# Control_Board.net
KiCad netlist of a schematic drawn in EAGLE
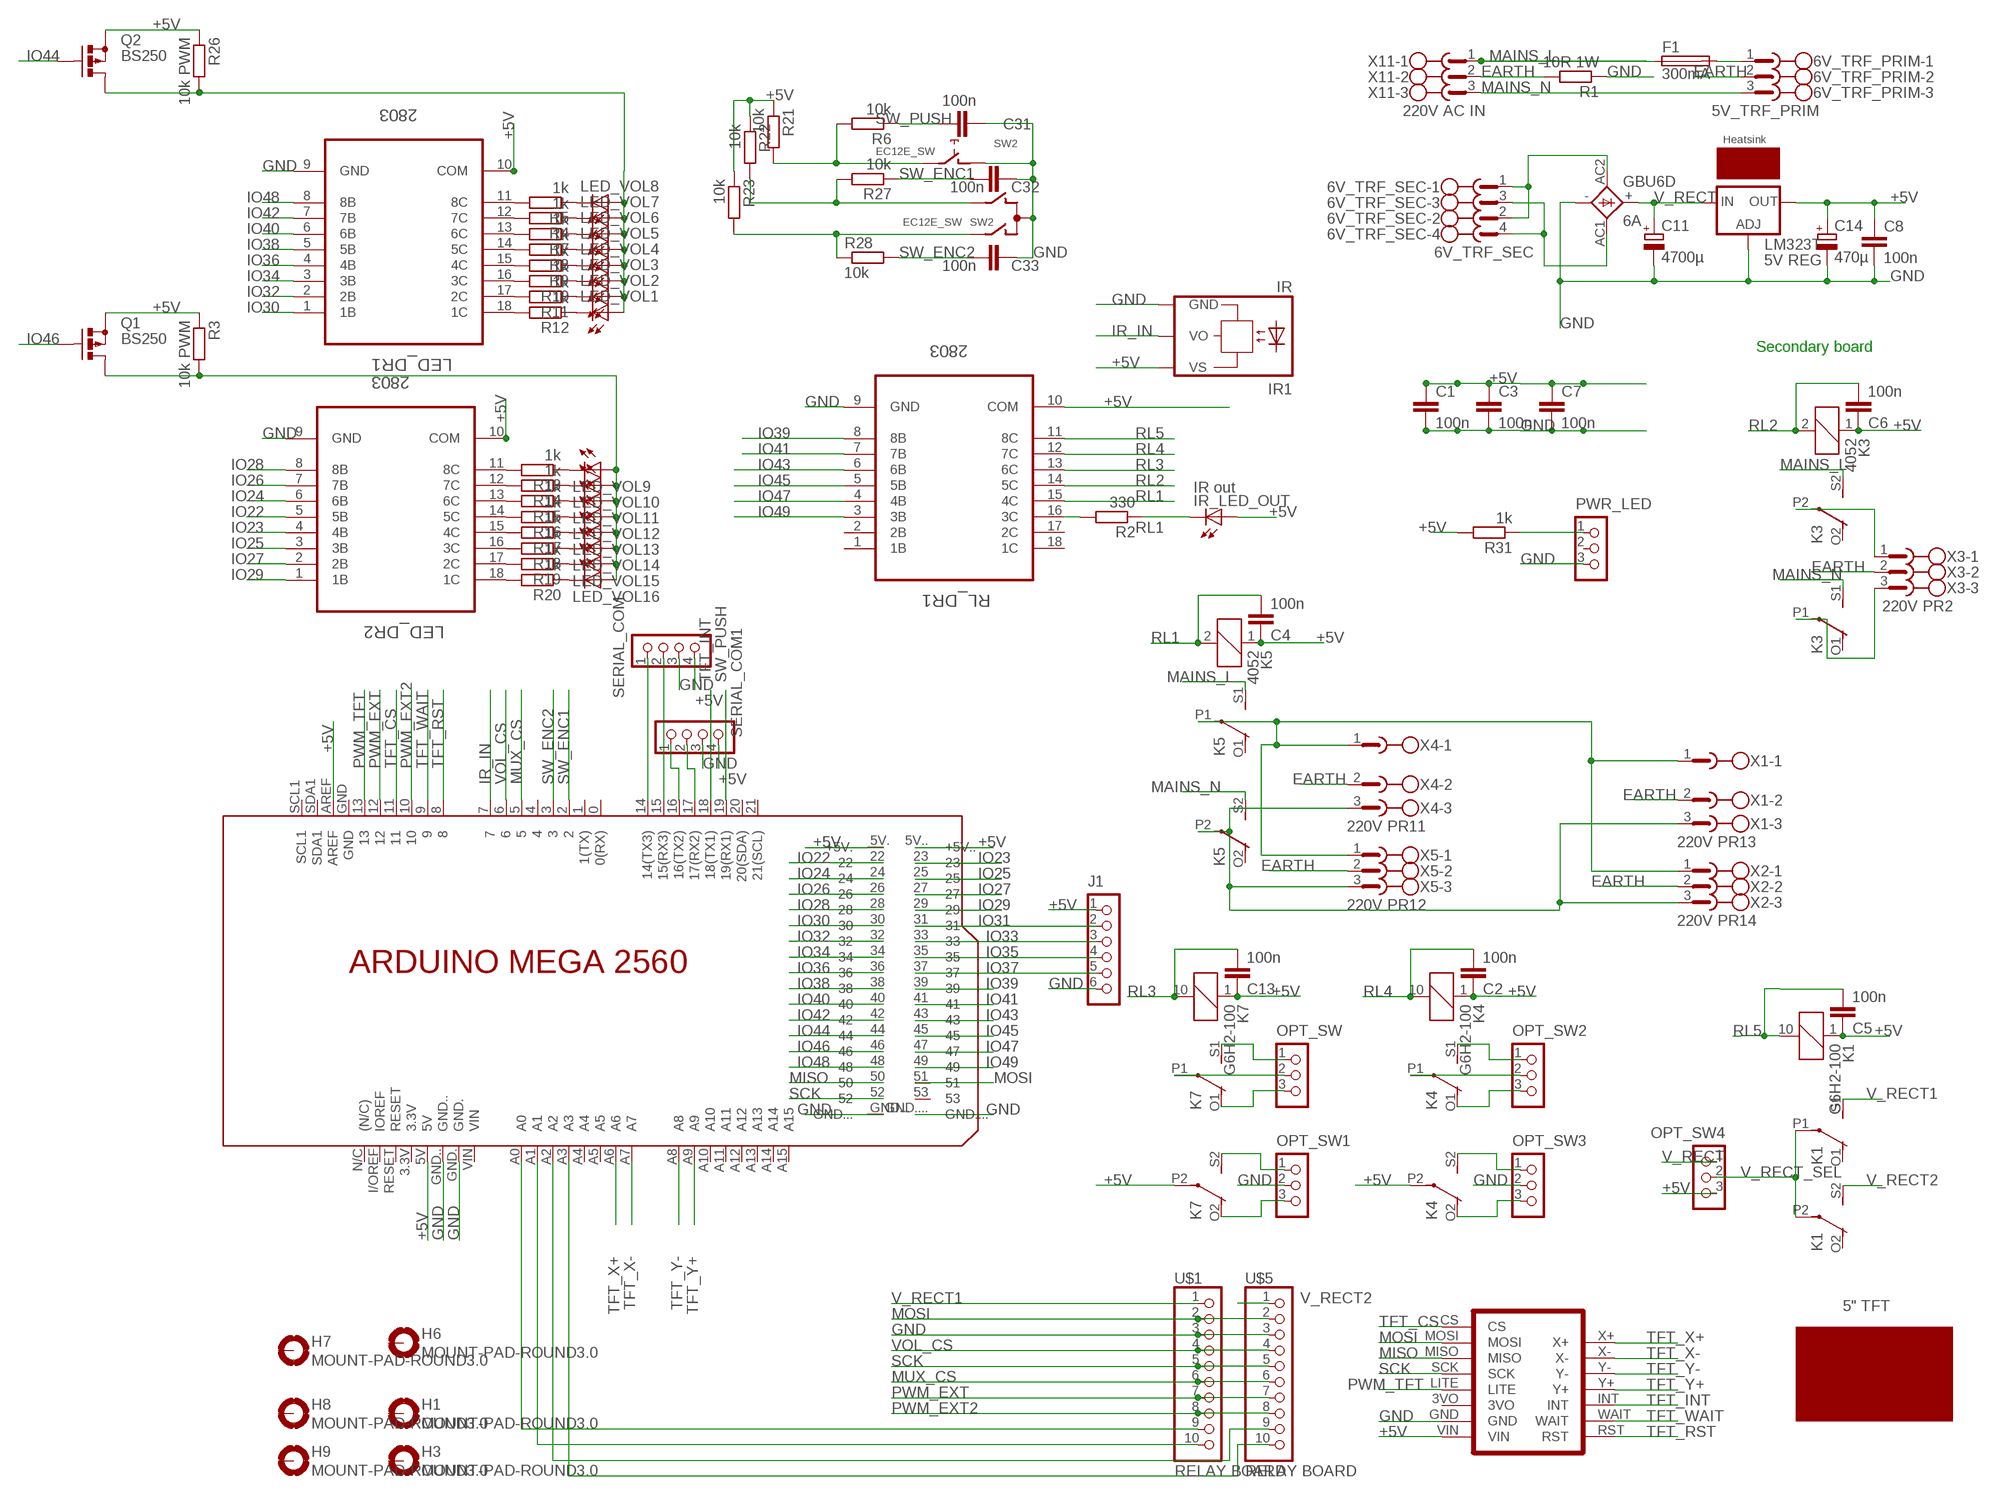
[diagram p0: schematic, sheet 1]

(export (version "E")
  (design (tool "Eeschema 10.0.6"))
  (components
    (comp (ref "6V_TRF_PRIM")
      (value "5V_TRF_PRIM")
      (footprint "eagle-import:MSTBV3")
      (fields
        (field (name "MPN") "MSTBV 2,5/3-GF-5.08")
        (field (name "MPN_1") "MSTBV 2,5/3-GF-5.08")
        (field (name "OC_FARNELL") "1792793")
        (field (name "OC_NEWARK") "69R9846")
      )
      (libsource (lib "eagle-import") (part "MSTBV3"))
    )
    (comp (ref "6V_TRF_SEC")
      (value "6V_TRF_SEC")
      (footprint "eagle-import:MSTBV4")
      (fields (field (name "MPN") "MSTBV 2,5/4-GF-5.08"))
      (libsource (lib "eagle-import") (part "MSTBV4"))
    )
    (comp (ref "C1")
      (value "100n")
      (footprint "eagle-import:C050-025X075")
      (libsource (lib "eagle-import") (part "C-EU050-025X075"))
    )
    (comp (ref "C2")
      (value "100n")
      (footprint "eagle-import:C050-025X075")
      (libsource (lib "eagle-import") (part "C-EU050-025X075"))
    )
    (comp (ref "C3")
      (value "100n")
      (footprint "eagle-import:C050-025X075")
      (libsource (lib "eagle-import") (part "C-EU050-025X075"))
    )
    (comp (ref "C4")
      (value "100n")
      (footprint "eagle-import:C050-025X075")
      (libsource (lib "eagle-import") (part "C-EU050-025X075"))
    )
    (comp (ref "C5")
      (value "100n")
      (footprint "eagle-import:C050-025X075")
      (libsource (lib "eagle-import") (part "C-EU050-025X075"))
    )
    (comp (ref "C6")
      (value "100n")
      (footprint "eagle-import:C050-025X075")
      (libsource (lib "eagle-import") (part "C-EU050-025X075"))
    )
    (comp (ref "C7")
      (value "100n")
      (footprint "eagle-import:C050-025X075")
      (libsource (lib "eagle-import") (part "C-EU050-025X075"))
    )
    (comp (ref "C8")
      (value "100n")
      (footprint "eagle-import:C050-025X075")
      (libsource (lib "eagle-import") (part "C-EU050-025X075"))
    )
    (comp (ref "C11")
      (value "4700µ")
      (footprint "eagle-import:E7,5-16")
      (libsource (lib "eagle-import") (part "CPOL-EUE7.5-16"))
    )
    (comp (ref "C13")
      (value "100n")
      (footprint "eagle-import:C050-025X075")
      (libsource (lib "eagle-import") (part "C-EU050-025X075"))
    )
    (comp (ref "C14")
      (value "470µ")
      (footprint "eagle-import:E2,5-6")
      (libsource (lib "eagle-import") (part "CPOL-EUE2.5-6"))
    )
    (comp (ref "C31")
      (value "100n")
      (footprint "eagle-import:C050-025X075")
      (libsource (lib "eagle-import") (part "C-EU050-025X075"))
    )
    (comp (ref "C32")
      (value "100n")
      (footprint "eagle-import:C050-025X075")
      (libsource (lib "eagle-import") (part "C-EU050-025X075"))
    )
    (comp (ref "C33")
      (value "100n")
      (footprint "eagle-import:C050-025X075")
      (libsource (lib "eagle-import") (part "C-EU050-025X075"))
    )
    (comp (ref "F1")
      (value "300mA")
      (footprint "eagle-import:GSH15")
      (fields (field (name "MPN") "64900001039"))
      (libsource (lib "eagle-import") (part "GSH15"))
    )
    (comp (ref "GBU6D")
      (value "6A")
      (footprint "eagle-import:GBU4S")
      (libsource (lib "eagle-import") (part "GBU4"))
    )
    (comp (ref "H1")
      (value "MOUNT-PAD-ROUND3.0")
      (footprint "eagle-import:3,0-PAD")
      (libsource (lib "eagle-import") (part "MOUNT-PAD-ROUND3.0"))
    )
    (comp (ref "H3")
      (value "MOUNT-PAD-ROUND3.0")
      (footprint "eagle-import:3,0-PAD")
      (libsource (lib "eagle-import") (part "MOUNT-PAD-ROUND3.0"))
    )
    (comp (ref "H6")
      (value "MOUNT-PAD-ROUND3.0")
      (footprint "eagle-import:3,0-PAD")
      (libsource (lib "eagle-import") (part "MOUNT-PAD-ROUND3.0"))
    )
    (comp (ref "H7")
      (value "MOUNT-PAD-ROUND3.0")
      (footprint "eagle-import:3,0-PAD")
      (libsource (lib "eagle-import") (part "MOUNT-PAD-ROUND3.0"))
    )
    (comp (ref "H8")
      (value "MOUNT-PAD-ROUND3.0")
      (footprint "eagle-import:3,0-PAD")
      (libsource (lib "eagle-import") (part "MOUNT-PAD-ROUND3.0"))
    )
    (comp (ref "H9")
      (value "MOUNT-PAD-ROUND3.0")
      (footprint "eagle-import:3,0-PAD")
      (libsource (lib "eagle-import") (part "MOUNT-PAD-ROUND3.0"))
    )
    (comp (ref "IR1")
      (value "IR")
      (footprint "eagle-import:TSOP17_TB1")
      (libsource (lib "eagle-import") (part "TSOP17TB138"))
    )
    (comp (ref "IR_LED_OUT")
      (value "IR out")
      (footprint "eagle-import:LED3MM")
      (fields
        (field (name "MF") "VISHAY SEMICONDUCTOR")
        (field (name "MF_1") "VISHAY SEMICONDUCTOR")
        (field (name "OC_FARNELL") "1612435")
      )
      (libsource (lib "eagle-import") (part "TLLG4400"))
    )
    (comp (ref "J1")
      (value "CON_HEADER_1X06-PTH")
      (footprint "eagle-import:M1X6")
      (libsource (lib "eagle-import") (part "CON_HEADER_1X06-PTH"))
    )
    (comp (ref "K1")
      (value "G6H2-100")
      (footprint "eagle-import:G6H2-100")
      (fields (field (name "OC_FARNELL") "unknown") (field (name "OC_NEWARK") "unknown"))
      (libsource (lib "eagle-import") (part "G6H2-100"))
    )
    (comp (ref "K3")
      (value "4052")
      (footprint "eagle-import:F4052")
      (libsource (lib "eagle-import") (part "4052"))
    )
    (comp (ref "K4")
      (value "G6H2-100")
      (footprint "eagle-import:G6H2-100")
      (libsource (lib "eagle-import") (part "G6H2-100"))
    )
    (comp (ref "K5")
      (value "4052")
      (footprint "eagle-import:F4052")
      (libsource (lib "eagle-import") (part "4052"))
    )
    (comp (ref "K7")
      (value "G6H2-100")
      (footprint "eagle-import:G6H2-100")
      (libsource (lib "eagle-import") (part "G6H2-100"))
    )
    (comp (ref "LED_DR1")
      (value "2803")
      (footprint "eagle-import:SOIC127P1030X265-18N")
      (fields
        (field (name "MPN") "ULN2803ADWR")
        (field (name "MPN_1") "ULN2803ADWR")
        (field (name "OC_FARNELL") "1652420")
        (field (name "OC_NEWARK") "87H4769")
        (field (name "PACKAGE") "SOIC-18")
        (field (name "SUPPLIER") "TEXAS INSTRUMENTS")
      )
      (libsource (lib "eagle-import") (part "ULN2803ADWR"))
    )
    (comp (ref "LED_DR2")
      (value "2803")
      (footprint "eagle-import:SOIC127P1030X265-18N")
      (fields
        (field (name "MPN") "ULN2803ADWR")
        (field (name "MPN_1") "ULN2803ADWR")
        (field (name "OC_FARNELL") "1652420")
        (field (name "OC_NEWARK") "87H4769")
        (field (name "PACKAGE") "SOIC-18")
        (field (name "SUPPLIER") "TEXAS INSTRUMENTS")
      )
      (libsource (lib "eagle-import") (part "ULN2803ADWR"))
    )
    (comp (ref "LED_VOL1")
      (value "TLLG4400")
      (footprint "eagle-import:LED3MM")
      (fields
        (field (name "MF") "VISHAY SEMICONDUCTOR")
        (field (name "MF_1") "VISHAY SEMICONDUCTOR")
        (field (name "OC_FARNELL") "1612435")
      )
      (libsource (lib "eagle-import") (part "TLLG4400"))
    )
    (comp (ref "LED_VOL2")
      (value "TLLG4400")
      (footprint "eagle-import:LED3MM")
      (fields
        (field (name "MF") "VISHAY SEMICONDUCTOR")
        (field (name "MF_1") "VISHAY SEMICONDUCTOR")
        (field (name "OC_FARNELL") "1612435")
      )
      (libsource (lib "eagle-import") (part "TLLG4400"))
    )
    (comp (ref "LED_VOL3")
      (value "TLLG4400")
      (footprint "eagle-import:LED3MM")
      (fields
        (field (name "MF") "VISHAY SEMICONDUCTOR")
        (field (name "MF_1") "VISHAY SEMICONDUCTOR")
        (field (name "OC_FARNELL") "1612435")
      )
      (libsource (lib "eagle-import") (part "TLLG4400"))
    )
    (comp (ref "LED_VOL4")
      (value "TLLG4400")
      (footprint "eagle-import:LED3MM")
      (fields
        (field (name "MF") "VISHAY SEMICONDUCTOR")
        (field (name "MF_1") "VISHAY SEMICONDUCTOR")
        (field (name "OC_FARNELL") "1612435")
      )
      (libsource (lib "eagle-import") (part "TLLG4400"))
    )
    (comp (ref "LED_VOL5")
      (value "TLLG4400")
      (footprint "eagle-import:LED3MM")
      (fields
        (field (name "MF") "VISHAY SEMICONDUCTOR")
        (field (name "MF_1") "VISHAY SEMICONDUCTOR")
        (field (name "OC_FARNELL") "1612435")
      )
      (libsource (lib "eagle-import") (part "TLLG4400"))
    )
    (comp (ref "LED_VOL6")
      (value "TLLG4400")
      (footprint "eagle-import:LED3MM")
      (fields
        (field (name "MF") "VISHAY SEMICONDUCTOR")
        (field (name "MF_1") "VISHAY SEMICONDUCTOR")
        (field (name "OC_FARNELL") "1612435")
      )
      (libsource (lib "eagle-import") (part "TLLG4400"))
    )
    (comp (ref "LED_VOL7")
      (value "TLLG4400")
      (footprint "eagle-import:LED3MM")
      (fields
        (field (name "MF") "VISHAY SEMICONDUCTOR")
        (field (name "MF_1") "VISHAY SEMICONDUCTOR")
        (field (name "OC_FARNELL") "1612435")
      )
      (libsource (lib "eagle-import") (part "TLLG4400"))
    )
    (comp (ref "LED_VOL8")
      (value "TLLG4400")
      (footprint "eagle-import:LED3MM")
      (fields
        (field (name "MF") "VISHAY SEMICONDUCTOR")
        (field (name "MF_1") "VISHAY SEMICONDUCTOR")
        (field (name "OC_FARNELL") "1612435")
      )
      (libsource (lib "eagle-import") (part "TLLG4400"))
    )
    (comp (ref "LED_VOL9")
      (value "TLLG4400")
      (footprint "eagle-import:LED3MM")
      (fields
        (field (name "MF") "VISHAY SEMICONDUCTOR")
        (field (name "MF_1") "VISHAY SEMICONDUCTOR")
        (field (name "OC_FARNELL") "1612435")
      )
      (libsource (lib "eagle-import") (part "TLLG4400"))
    )
    (comp (ref "LED_VOL10")
      (value "TLLG4400")
      (footprint "eagle-import:LED3MM")
      (fields
        (field (name "MF") "VISHAY SEMICONDUCTOR")
        (field (name "MF_1") "VISHAY SEMICONDUCTOR")
        (field (name "OC_FARNELL") "1612435")
      )
      (libsource (lib "eagle-import") (part "TLLG4400"))
    )
    (comp (ref "LED_VOL11")
      (value "TLLG4400")
      (footprint "eagle-import:LED3MM")
      (fields
        (field (name "MF") "VISHAY SEMICONDUCTOR")
        (field (name "MF_1") "VISHAY SEMICONDUCTOR")
        (field (name "OC_FARNELL") "1612435")
      )
      (libsource (lib "eagle-import") (part "TLLG4400"))
    )
    (comp (ref "LED_VOL12")
      (value "TLLG4400")
      (footprint "eagle-import:LED3MM")
      (fields
        (field (name "MF") "VISHAY SEMICONDUCTOR")
        (field (name "MF_1") "VISHAY SEMICONDUCTOR")
        (field (name "OC_FARNELL") "1612435")
      )
      (libsource (lib "eagle-import") (part "TLLG4400"))
    )
    (comp (ref "LED_VOL13")
      (value "TLLG4400")
      (footprint "eagle-import:LED3MM")
      (fields
        (field (name "MF") "VISHAY SEMICONDUCTOR")
        (field (name "MF_1") "VISHAY SEMICONDUCTOR")
        (field (name "OC_FARNELL") "1612435")
      )
      (libsource (lib "eagle-import") (part "TLLG4400"))
    )
    (comp (ref "LED_VOL14")
      (value "TLLG4400")
      (footprint "eagle-import:LED3MM")
      (fields
        (field (name "MF") "VISHAY SEMICONDUCTOR")
        (field (name "MF_1") "VISHAY SEMICONDUCTOR")
        (field (name "OC_FARNELL") "1612435")
      )
      (libsource (lib "eagle-import") (part "TLLG4400"))
    )
    (comp (ref "LED_VOL15")
      (value "TLLG4400")
      (footprint "eagle-import:LED3MM")
      (fields
        (field (name "MF") "VISHAY SEMICONDUCTOR")
        (field (name "MF_1") "VISHAY SEMICONDUCTOR")
        (field (name "OC_FARNELL") "1612435")
      )
      (libsource (lib "eagle-import") (part "TLLG4400"))
    )
    (comp (ref "LED_VOL16")
      (value "TLLG4400")
      (footprint "eagle-import:LED3MM")
      (fields
        (field (name "MF") "VISHAY SEMICONDUCTOR")
        (field (name "MF_1") "VISHAY SEMICONDUCTOR")
        (field (name "OC_FARNELL") "1612435")
      )
      (libsource (lib "eagle-import") (part "TLLG4400"))
    )
    (comp (ref "LM323T")
      (value "5V REG")
      (footprint "eagle-import:TO220S")
      (libsource (lib "eagle-import") (part "LM138-TSTO220S_IAO"))
    )
    (comp (ref "OPT_SW")
      (value "CON_HEADER_1X03-PTH")
      (footprint "eagle-import:M1X3")
      (libsource (lib "eagle-import") (part "CON_HEADER_1X03-PTH"))
    )
    (comp (ref "OPT_SW1")
      (value "CON_HEADER_1X03-PTH")
      (footprint "eagle-import:M1X3")
      (libsource (lib "eagle-import") (part "CON_HEADER_1X03-PTH"))
    )
    (comp (ref "OPT_SW2")
      (value "CON_HEADER_1X03-PTH")
      (footprint "eagle-import:M1X3")
      (libsource (lib "eagle-import") (part "CON_HEADER_1X03-PTH"))
    )
    (comp (ref "OPT_SW3")
      (value "CON_HEADER_1X03-PTH")
      (footprint "eagle-import:M1X3")
      (libsource (lib "eagle-import") (part "CON_HEADER_1X03-PTH"))
    )
    (comp (ref "OPT_SW4")
      (value "V_RECT_-_5V_OUT")
      (footprint "eagle-import:M1X3")
      (libsource (lib "eagle-import") (part "CON_HEADER_1X03-PTH"))
    )
    (comp (ref "PCB2")
      (value "ARDUINO_MEGA2560_INV")
      (footprint "eagle-import:ARDUINO_MEGA2560_INV")
      (libsource (lib "eagle-import") (part "ARDUINO_MEGA2560_INV"))
    )
    (comp (ref "PWR_LED")
      (value "CON_HEADER_1X03-PTH")
      (footprint "eagle-import:M1X3")
      (libsource (lib "eagle-import") (part "CON_HEADER_1X03-PTH"))
    )
    (comp (ref "Q1")
      (value "BS250")
      (footprint "eagle-import:SOT54E")
      (libsource (lib "eagle-import") (part "BS250"))
    )
    (comp (ref "Q2")
      (value "BS250")
      (footprint "eagle-import:SOT54E")
      (libsource (lib "eagle-import") (part "BS250"))
    )
    (comp (ref "R1")
      (value "10R 1W")
      (footprint "eagle-import:0411_15")
      (libsource (lib "eagle-import") (part "R-EU_0411/15"))
    )
    (comp (ref "R2")
      (value "330")
      (footprint "eagle-import:0207_10")
      (libsource (lib "eagle-import") (part "R-EU_0207/10"))
    )
    (comp (ref "R3")
      (value "10k PWM")
      (footprint "eagle-import:0207_10")
      (libsource (lib "eagle-import") (part "R-EU_0207/10"))
    )
    (comp (ref "R4")
      (value "1k")
      (footprint "eagle-import:0207_10")
      (libsource (lib "eagle-import") (part "R-EU_0207/10"))
    )
    (comp (ref "R5")
      (value "1k")
      (footprint "eagle-import:0207_10")
      (libsource (lib "eagle-import") (part "R-EU_0207/10"))
    )
    (comp (ref "R6")
      (value "10k")
      (footprint "eagle-import:0207_10")
      (libsource (lib "eagle-import") (part "R-EU_0207/10"))
    )
    (comp (ref "R7")
      (value "1k")
      (footprint "eagle-import:0207_10")
      (libsource (lib "eagle-import") (part "R-EU_0207/10"))
    )
    (comp (ref "R8")
      (value "1k")
      (footprint "eagle-import:0207_10")
      (libsource (lib "eagle-import") (part "R-EU_0207/10"))
    )
    (comp (ref "R9")
      (value "1k")
      (footprint "eagle-import:0207_10")
      (libsource (lib "eagle-import") (part "R-EU_0207/10"))
    )
    (comp (ref "R10")
      (value "1k")
      (footprint "eagle-import:0207_10")
      (libsource (lib "eagle-import") (part "R-EU_0207/10"))
    )
    (comp (ref "R11")
      (value "1k")
      (footprint "eagle-import:0207_10")
      (libsource (lib "eagle-import") (part "R-EU_0207/10"))
    )
    (comp (ref "R12")
      (value "1k")
      (footprint "eagle-import:0207_10")
      (libsource (lib "eagle-import") (part "R-EU_0207/10"))
    )
    (comp (ref "R13")
      (value "1k")
      (footprint "eagle-import:0207_10")
      (libsource (lib "eagle-import") (part "R-EU_0207/10"))
    )
    (comp (ref "R14")
      (value "1k")
      (footprint "eagle-import:0207_10")
      (libsource (lib "eagle-import") (part "R-EU_0207/10"))
    )
    (comp (ref "R15")
      (value "1k")
      (footprint "eagle-import:0207_10")
      (libsource (lib "eagle-import") (part "R-EU_0207/10"))
    )
    (comp (ref "R16")
      (value "1k")
      (footprint "eagle-import:0207_10")
      (libsource (lib "eagle-import") (part "R-EU_0207/10"))
    )
    (comp (ref "R17")
      (value "1k")
      (footprint "eagle-import:0207_10")
      (libsource (lib "eagle-import") (part "R-EU_0207/10"))
    )
    (comp (ref "R18")
      (value "1k")
      (footprint "eagle-import:0207_10")
      (libsource (lib "eagle-import") (part "R-EU_0207/10"))
    )
    (comp (ref "R19")
      (value "1k")
      (footprint "eagle-import:0207_10")
      (libsource (lib "eagle-import") (part "R-EU_0207/10"))
    )
    (comp (ref "R20")
      (value "1k")
      (footprint "eagle-import:0207_10")
      (libsource (lib "eagle-import") (part "R-EU_0207/10"))
    )
    (comp (ref "R21")
      (value "10k")
      (footprint "eagle-import:0207_10")
      (libsource (lib "eagle-import") (part "R-EU_0207/10"))
    )
    (comp (ref "R22")
      (value "10k")
      (footprint "eagle-import:0207_10")
      (libsource (lib "eagle-import") (part "R-EU_0207/10"))
    )
    (comp (ref "R23")
      (value "10k")
      (footprint "eagle-import:0207_10")
      (libsource (lib "eagle-import") (part "R-EU_0207/10"))
    )
    (comp (ref "R26")
      (value "10k PWM")
      (footprint "eagle-import:0207_10")
      (libsource (lib "eagle-import") (part "R-EU_0207/10"))
    )
    (comp (ref "R27")
      (value "10k")
      (footprint "eagle-import:0207_10")
      (libsource (lib "eagle-import") (part "R-EU_0207/10"))
    )
    (comp (ref "R28")
      (value "10k")
      (footprint "eagle-import:0207_10")
      (libsource (lib "eagle-import") (part "R-EU_0207/10"))
    )
    (comp (ref "R31")
      (value "1k")
      (footprint "eagle-import:0207_10")
      (libsource (lib "eagle-import") (part "R-EU_0207/10"))
    )
    (comp (ref "RL_DR1")
      (value "2803")
      (footprint "eagle-import:SOIC127P1030X265-18N")
      (fields
        (field (name "MPN") "ULN2803ADWR")
        (field (name "MPN_1") "ULN2803ADWR")
        (field (name "OC_FARNELL") "1652420")
        (field (name "OC_NEWARK") "87H4769")
        (field (name "PACKAGE") "SOIC-18")
        (field (name "SUPPLIER") "TEXAS INSTRUMENTS")
      )
      (libsource (lib "eagle-import") (part "ULN2803ADWR"))
    )
    (comp (ref "SERIAL_COM")
      (value "CON_HEADER_1X04")
      (footprint "eagle-import:M1X4")
      (libsource (lib "eagle-import") (part "CON_HEADER_1X04"))
    )
    (comp (ref "SERIAL_COM1")
      (value "CON_HEADER_1X04")
      (footprint "eagle-import:M1X4")
      (libsource (lib "eagle-import") (part "CON_HEADER_1X04"))
    )
    (comp (ref "SW2")
      (value "EC12E_SW")
      (footprint "eagle-import:ALPS_EC12E_SW")
      (fields (field (name "MPN") "EC12E2424407"))
      (libsource (lib "eagle-import") (part "EC12E_SW"))
    )
    (comp (ref "U$1")
      (value "RELAY BOARD")
      (footprint "eagle-import:1X10-BIG")
      (libsource (lib "eagle-import") (part "PINHD-1X10"))
    )
    (comp (ref "U$2")
      (value "HEATSINK")
      (footprint "eagle-import:HEATSINK")
      (libsource (lib "eagle-import") (part "HEATSINK"))
    )
    (comp (ref "U$3")
      (value "RA8875")
      (footprint "eagle-import:RA8875")
      (libsource (lib "eagle-import") (part "RA8875"))
    )
    (comp (ref "U$4")
      (value "5\"TFT")
      (footprint "eagle-import:5_TFT")
      (libsource (lib "eagle-import") (part "5{dblquote}TFT"))
    )
    (comp (ref "U$5")
      (value "RELAY BOARD")
      (footprint "eagle-import:1X10-BIG")
      (libsource (lib "eagle-import") (part "PINHD-1X10"))
    )
    (comp (ref "X1")
      (value "220V PR13")
      (footprint "eagle-import:MSTBV3")
      (fields (field (name "MPN") "MSTBV 2,5/3-GF-5.08"))
      (libsource (lib "eagle-import") (part "MSTBV3"))
    )
    (comp (ref "X2")
      (value "220V PR14")
      (footprint "eagle-import:MSTBV3")
      (fields
        (field (name "MPN") "MSTBV 2,5/3-GF-5.08")
        (field (name "MPN_1") "MSTBV 2,5/3-GF-5.08")
        (field (name "OC_FARNELL") "1792793")
        (field (name "OC_NEWARK") "69R9846")
      )
      (libsource (lib "eagle-import") (part "MSTBV3"))
    )
    (comp (ref "X3")
      (value "220V PR2")
      (footprint "eagle-import:MSTBV3")
      (fields (field (name "MPN") "MSTBV 2,5/3-GF-5.08"))
      (libsource (lib "eagle-import") (part "MSTBV3"))
    )
    (comp (ref "X4")
      (value "220V PR11")
      (footprint "eagle-import:MSTBV3")
      (fields
        (field (name "MPN") "MSTBV 2,5/3-GF-5.08")
        (field (name "MPN_1") "MSTBV 2,5/3-GF-5.08")
        (field (name "OC_FARNELL") "1792793")
        (field (name "OC_NEWARK") "69R9846")
      )
      (libsource (lib "eagle-import") (part "MSTBV3"))
    )
    (comp (ref "X5")
      (value "220V PR12")
      (footprint "eagle-import:MSTBV3")
      (fields
        (field (name "MPN") "MSTBV 2,5/3-GF-5.08")
        (field (name "MPN_1") "MSTBV 2,5/3-GF-5.08")
        (field (name "OC_FARNELL") "1792793")
        (field (name "OC_NEWARK") "69R9846")
      )
      (libsource (lib "eagle-import") (part "MSTBV3"))
    )
    (comp (ref "X11")
      (value "220V AC IN")
      (footprint "eagle-import:MSTBV3")
      (fields (field (name "MPN") "MSTBV 2,5/3-GF-5.08"))
      (libsource (lib "eagle-import") (part "MSTBV3"))
    )
  )
  (nets
    (net (code "1") (name "/+5V") (class "Default")
      (node (ref "C1") (pin "1") (pinfunction "1_1") (pintype "passive"))
      (node (ref "C13") (pin "1") (pinfunction "1_1") (pintype "passive"))
      (node (ref "C14") (pin "+") (pinfunction "+_+") (pintype "passive"))
      (node (ref "C2") (pin "1") (pinfunction "1_1") (pintype "passive"))
      (node (ref "C3") (pin "1") (pinfunction "1_1") (pintype "passive"))
      (node (ref "C4") (pin "1") (pinfunction "1_1") (pintype "passive"))
      (node (ref "C5") (pin "1") (pinfunction "1_1") (pintype "passive"))
      (node (ref "C6") (pin "1") (pinfunction "1_1") (pintype "passive"))
      (node (ref "C7") (pin "1") (pinfunction "1_1") (pintype "passive"))
      (node (ref "C8") (pin "1") (pinfunction "1_1") (pintype "passive"))
      (node (ref "IR1") (pin "VS") (pinfunction "VS_VS") (pintype "power_in"))
      (node (ref "IR_LED_OUT") (pin "A") (pinfunction "A_A") (pintype "passive"))
      (node (ref "J1") (pin "1") (pinfunction "1_1") (pintype "bidirectional"))
      (node (ref "K1") (pin "1") (pinfunction "1_1") (pintype "passive"))
      (node (ref "K3") (pin "1") (pinfunction "1_1") (pintype "passive"))
      (node (ref "K4") (pin "1") (pinfunction "1_1") (pintype "passive"))
      (node (ref "K4") (pin "P2") (pinfunction "P_P2") (pintype "passive"))
      (node (ref "K5") (pin "1") (pinfunction "1_1") (pintype "passive"))
      (node (ref "K7") (pin "1") (pinfunction "1_1") (pintype "passive"))
      (node (ref "K7") (pin "P2") (pinfunction "P_P2") (pintype "passive"))
      (node (ref "LED_DR1") (pin "10") (pinfunction "COM_10") (pintype "output"))
      (node (ref "LED_DR2") (pin "10") (pinfunction "COM_10") (pintype "output"))
      (node (ref "LM323T") (pin "3") (pinfunction "OUT_3") (pintype "passive"))
      (node (ref "OPT_SW4") (pin "3") (pinfunction "3_3") (pintype "bidirectional"))
      (node (ref "PCB2") (pin "5V") (pinfunction "5V_5V") (pintype "bidirectional"))
      (node (ref "PCB2") (pin "5V.") (pinfunction "+5V._5V.") (pintype "bidirectional"))
      (node (ref "PCB2") (pin "5V..") (pinfunction "+5V.._5V..") (pintype "bidirectional"))
      (node (ref "PCB2") (pin "AREF") (pinfunction "AREF_AREF") (pintype "bidirectional"))
      (node (ref "Q1") (pin "S") (pinfunction "S_S") (pintype "passive"))
      (node (ref "Q2") (pin "S") (pinfunction "S_S") (pintype "passive"))
      (node (ref "R21") (pin "1") (pinfunction "1_1") (pintype "passive"))
      (node (ref "R22") (pin "1") (pinfunction "1_1") (pintype "passive"))
      (node (ref "R23") (pin "1") (pinfunction "1_1") (pintype "passive"))
      (node (ref "R26") (pin "1") (pinfunction "1_1") (pintype "passive"))
      (node (ref "R3") (pin "1") (pinfunction "1_1") (pintype "passive"))
      (node (ref "R31") (pin "2") (pinfunction "2_2") (pintype "passive"))
      (node (ref "RL_DR1") (pin "10") (pinfunction "COM_10") (pintype "output"))
      (node (ref "SERIAL_COM") (pin "4") (pinfunction "4_4") (pintype "bidirectional"))
      (node (ref "SERIAL_COM1") (pin "4") (pinfunction "4_4") (pintype "bidirectional"))
      (node (ref "U$3") (pin "VIN") (pinfunction "VIN_VIN") (pintype "bidirectional"))
    )
    (net (code "2") (name "/EARTH") (class "Default")
      (node (ref "6V_TRF_PRIM") (pin "2") (pinfunction "1_2") (pintype "passive"))
      (node (ref "R1") (pin "2") (pinfunction "2_2") (pintype "passive"))
      (node (ref "X1") (pin "2") (pinfunction "1_2") (pintype "passive"))
      (node (ref "X11") (pin "2") (pinfunction "1_2") (pintype "passive"))
      (node (ref "X2") (pin "2") (pinfunction "1_2") (pintype "passive"))
      (node (ref "X3") (pin "2") (pinfunction "1_2") (pintype "passive"))
      (node (ref "X4") (pin "2") (pinfunction "1_2") (pintype "passive"))
      (node (ref "X5") (pin "2") (pinfunction "1_2") (pintype "passive"))
    )
    (net (code "3") (name "/GND") (class "Default")
      (node (ref "C1") (pin "2") (pinfunction "2_2") (pintype "passive"))
      (node (ref "C11") (pin "-") (pinfunction "-_-") (pintype "passive"))
      (node (ref "C14") (pin "-") (pinfunction "-_-") (pintype "passive"))
      (node (ref "C3") (pin "2") (pinfunction "2_2") (pintype "passive"))
      (node (ref "C31") (pin "1") (pinfunction "1_1") (pintype "passive"))
      (node (ref "C32") (pin "1") (pinfunction "1_1") (pintype "passive"))
      (node (ref "C33") (pin "1") (pinfunction "1_1") (pintype "passive"))
      (node (ref "C7") (pin "2") (pinfunction "2_2") (pintype "passive"))
      (node (ref "C8") (pin "2") (pinfunction "2_2") (pintype "passive"))
      (node (ref "GBU6D") (pin "-") (pinfunction "-_-") (pintype "passive"))
      (node (ref "IR1") (pin "GND") (pinfunction "GND_GND") (pintype "power_in"))
      (node (ref "J1") (pin "6") (pinfunction "6_6") (pintype "passive"))
      (node (ref "LED_DR1") (pin "9") (pinfunction "GND_9") (pintype "passive"))
      (node (ref "LED_DR2") (pin "9") (pinfunction "GND_9") (pintype "passive"))
      (node (ref "LM323T") (pin "2") (pinfunction "ADJ_2") (pintype "input"))
      (node (ref "OPT_SW1") (pin "2") (pinfunction "2_2") (pintype "bidirectional"))
      (node (ref "OPT_SW3") (pin "2") (pinfunction "2_2") (pintype "bidirectional"))
      (node (ref "PCB2") (pin "GND.") (pinfunction "GND._GND.") (pintype "bidirectional"))
      (node (ref "PCB2") (pin "GND..") (pinfunction "GND.._GND..") (pintype "bidirectional"))
      (node (ref "PCB2") (pin "GND...") (pinfunction "GND..._GND...") (pintype "bidirectional"))
      (node (ref "PCB2") (pin "GND....") (pinfunction "GND...._GND....") (pintype "bidirectional"))
      (node (ref "PWR_LED") (pin "3") (pinfunction "3_3") (pintype "bidirectional"))
      (node (ref "R1") (pin "1") (pinfunction "1_1") (pintype "passive"))
      (node (ref "RL_DR1") (pin "9") (pinfunction "GND_9") (pintype "passive"))
      (node (ref "SERIAL_COM") (pin "3") (pinfunction "3_3") (pintype "bidirectional"))
      (node (ref "SERIAL_COM1") (pin "3") (pinfunction "3_3") (pintype "bidirectional"))
      (node (ref "SW2") (pin "C") (pinfunction "C_C") (pintype "passive"))
      (node (ref "SW2") (pin "D") (pinfunction "1_D") (pintype "passive"))
      (node (ref "U$1") (pin "3") (pinfunction "3_3") (pintype "passive"))
      (node (ref "U$3") (pin "GND") (pinfunction "GND_GND") (pintype "bidirectional"))
      (node (ref "U$5") (pin "3") (pinfunction "3_3") (pintype "passive"))
    )
    (net (code "4") (name "/IO22") (class "Default")
      (node (ref "LED_DR2") (pin "5") (pinfunction "5B_5") (pintype "input"))
      (node (ref "PCB2") (pin "22") (pinfunction "22_22") (pintype "bidirectional"))
    )
    (net (code "5") (name "/IO23") (class "Default")
      (node (ref "LED_DR2") (pin "4") (pinfunction "4B_4") (pintype "input"))
      (node (ref "PCB2") (pin "23") (pinfunction "23_23") (pintype "bidirectional"))
    )
    (net (code "6") (name "/IO24") (class "Default")
      (node (ref "LED_DR2") (pin "6") (pinfunction "6B_6") (pintype "input"))
      (node (ref "PCB2") (pin "24") (pinfunction "24_24") (pintype "bidirectional"))
    )
    (net (code "7") (name "/IO25") (class "Default")
      (node (ref "LED_DR2") (pin "3") (pinfunction "3B_3") (pintype "input"))
      (node (ref "PCB2") (pin "25") (pinfunction "25_25") (pintype "bidirectional"))
    )
    (net (code "8") (name "/IO26") (class "Default")
      (node (ref "LED_DR2") (pin "7") (pinfunction "7B_7") (pintype "input"))
      (node (ref "PCB2") (pin "26") (pinfunction "26_26") (pintype "bidirectional"))
    )
    (net (code "9") (name "/IO27") (class "Default")
      (node (ref "LED_DR2") (pin "2") (pinfunction "2B_2") (pintype "input"))
      (node (ref "PCB2") (pin "27") (pinfunction "27_27") (pintype "bidirectional"))
    )
    (net (code "10") (name "/IO28") (class "Default")
      (node (ref "LED_DR2") (pin "8") (pinfunction "8B_8") (pintype "input"))
      (node (ref "PCB2") (pin "28") (pinfunction "28_28") (pintype "bidirectional"))
    )
    (net (code "11") (name "/IO29") (class "Default")
      (node (ref "LED_DR2") (pin "1") (pinfunction "1B_1") (pintype "input"))
      (node (ref "PCB2") (pin "29") (pinfunction "29_29") (pintype "bidirectional"))
    )
    (net (code "12") (name "/IO30") (class "Default")
      (node (ref "LED_DR1") (pin "1") (pinfunction "1B_1") (pintype "input"))
      (node (ref "PCB2") (pin "30") (pinfunction "30_30") (pintype "bidirectional"))
    )
    (net (code "13") (name "/IO31") (class "Default")
      (node (ref "J1") (pin "2") (pinfunction "2_2") (pintype "bidirectional"))
      (node (ref "PCB2") (pin "31") (pinfunction "31_31") (pintype "bidirectional"))
    )
    (net (code "14") (name "/IO32") (class "Default")
      (node (ref "LED_DR1") (pin "2") (pinfunction "2B_2") (pintype "input"))
      (node (ref "PCB2") (pin "32") (pinfunction "32_32") (pintype "bidirectional"))
    )
    (net (code "15") (name "/IO33") (class "Default")
      (node (ref "J1") (pin "3") (pinfunction "3_3") (pintype "passive"))
      (node (ref "PCB2") (pin "33") (pinfunction "33_33") (pintype "bidirectional"))
    )
    (net (code "16") (name "/IO34") (class "Default")
      (node (ref "LED_DR1") (pin "3") (pinfunction "3B_3") (pintype "input"))
      (node (ref "PCB2") (pin "34") (pinfunction "34_34") (pintype "bidirectional"))
    )
    (net (code "17") (name "/IO35") (class "Default")
      (node (ref "J1") (pin "4") (pinfunction "4_4") (pintype "passive"))
      (node (ref "PCB2") (pin "35") (pinfunction "35_35") (pintype "bidirectional"))
    )
    (net (code "18") (name "/IO36") (class "Default")
      (node (ref "LED_DR1") (pin "4") (pinfunction "4B_4") (pintype "input"))
      (node (ref "PCB2") (pin "36") (pinfunction "36_36") (pintype "bidirectional"))
    )
    (net (code "19") (name "/IO37") (class "Default")
      (node (ref "J1") (pin "5") (pinfunction "5_5") (pintype "passive"))
      (node (ref "PCB2") (pin "37") (pinfunction "37_37") (pintype "bidirectional"))
    )
    (net (code "20") (name "/IO38") (class "Default")
      (node (ref "LED_DR1") (pin "5") (pinfunction "5B_5") (pintype "input"))
      (node (ref "PCB2") (pin "38") (pinfunction "38_38") (pintype "bidirectional"))
    )
    (net (code "21") (name "/IO39") (class "Default")
      (node (ref "PCB2") (pin "39") (pinfunction "39_39") (pintype "bidirectional"))
      (node (ref "RL_DR1") (pin "8") (pinfunction "8B_8") (pintype "input"))
    )
    (net (code "22") (name "/IO40") (class "Default")
      (node (ref "LED_DR1") (pin "6") (pinfunction "6B_6") (pintype "input"))
      (node (ref "PCB2") (pin "40") (pinfunction "40_40") (pintype "bidirectional"))
    )
    (net (code "23") (name "/IO41") (class "Default")
      (node (ref "PCB2") (pin "41") (pinfunction "41_41") (pintype "bidirectional"))
      (node (ref "RL_DR1") (pin "7") (pinfunction "7B_7") (pintype "input"))
    )
    (net (code "24") (name "/IO42") (class "Default")
      (node (ref "LED_DR1") (pin "7") (pinfunction "7B_7") (pintype "input"))
      (node (ref "PCB2") (pin "42") (pinfunction "42_42") (pintype "bidirectional"))
    )
    (net (code "25") (name "/IO43") (class "Default")
      (node (ref "PCB2") (pin "43") (pinfunction "43_43") (pintype "bidirectional"))
      (node (ref "RL_DR1") (pin "6") (pinfunction "6B_6") (pintype "input"))
    )
    (net (code "26") (name "/IO44") (class "Default")
      (node (ref "PCB2") (pin "44") (pinfunction "44_44") (pintype "bidirectional"))
      (node (ref "Q2") (pin "G") (pinfunction "G_G") (pintype "passive"))
    )
    (net (code "27") (name "/IO45") (class "Default")
      (node (ref "PCB2") (pin "45") (pinfunction "45_45") (pintype "bidirectional"))
      (node (ref "RL_DR1") (pin "5") (pinfunction "5B_5") (pintype "input"))
    )
    (net (code "28") (name "/IO46") (class "Default")
      (node (ref "PCB2") (pin "46") (pinfunction "46_46") (pintype "bidirectional"))
      (node (ref "Q1") (pin "G") (pinfunction "G_G") (pintype "passive"))
    )
    (net (code "29") (name "/IO47") (class "Default")
      (node (ref "PCB2") (pin "47") (pinfunction "47_47") (pintype "bidirectional"))
      (node (ref "RL_DR1") (pin "4") (pinfunction "4B_4") (pintype "input"))
    )
    (net (code "30") (name "/IO48") (class "Default")
      (node (ref "LED_DR1") (pin "8") (pinfunction "8B_8") (pintype "input"))
      (node (ref "PCB2") (pin "48") (pinfunction "48_48") (pintype "bidirectional"))
    )
    (net (code "31") (name "/IO49") (class "Default")
      (node (ref "PCB2") (pin "49") (pinfunction "49_49") (pintype "bidirectional"))
      (node (ref "RL_DR1") (pin "3") (pinfunction "3B_3") (pintype "input"))
    )
    (net (code "32") (name "/IR_IN") (class "Default")
      (node (ref "IR1") (pin "VO") (pinfunction "VO_VO") (pintype "open_collector"))
      (node (ref "PCB2") (pin "7") (pinfunction "7_7") (pintype "bidirectional"))
    )
    (net (code "33") (name "/MAINS_L") (class "Default")
      (node (ref "F1") (pin "1") (pinfunction "1_1") (pintype "passive"))
      (node (ref "K3") (pin "S2") (pinfunction "S_S2") (pintype "passive"))
      (node (ref "K5") (pin "S1") (pinfunction "S_S1") (pintype "passive"))
      (node (ref "X11") (pin "1") (pinfunction "1_1") (pintype "passive"))
    )
    (net (code "34") (name "/MAINS_N") (class "Default")
      (node (ref "6V_TRF_PRIM") (pin "3") (pinfunction "1_3") (pintype "passive"))
      (node (ref "K3") (pin "S1") (pinfunction "S_S1") (pintype "passive"))
      (node (ref "K5") (pin "S2") (pinfunction "S_S2") (pintype "passive"))
      (node (ref "X11") (pin "3") (pinfunction "1_3") (pintype "passive"))
    )
    (net (code "35") (name "/MISO") (class "Default")
      (node (ref "PCB2") (pin "50") (pinfunction "50_50") (pintype "bidirectional"))
      (node (ref "U$3") (pin "MISO") (pinfunction "MISO_MISO") (pintype "bidirectional"))
    )
    (net (code "36") (name "/MOSI") (class "Default")
      (node (ref "PCB2") (pin "51") (pinfunction "51_51") (pintype "bidirectional"))
      (node (ref "U$1") (pin "2") (pinfunction "2_2") (pintype "passive"))
      (node (ref "U$3") (pin "MOSI") (pinfunction "MOSI_MOSI") (pintype "bidirectional"))
      (node (ref "U$5") (pin "2") (pinfunction "2_2") (pintype "passive"))
    )
    (net (code "37") (name "/MUX_CS") (class "Default")
      (node (ref "PCB2") (pin "5") (pinfunction "5_5") (pintype "bidirectional"))
      (node (ref "U$1") (pin "6") (pinfunction "6_6") (pintype "passive"))
      (node (ref "U$5") (pin "6") (pinfunction "6_6") (pintype "passive"))
    )
    (net (code "38") (name "/PWM_EXT") (class "Default")
      (node (ref "PCB2") (pin "12") (pinfunction "12_12") (pintype "bidirectional"))
      (node (ref "U$1") (pin "7") (pinfunction "7_7") (pintype "passive"))
      (node (ref "U$5") (pin "7") (pinfunction "7_7") (pintype "passive"))
    )
    (net (code "39") (name "/PWM_EXT2") (class "Default")
      (node (ref "PCB2") (pin "10") (pinfunction "10_10") (pintype "bidirectional"))
      (node (ref "U$1") (pin "8") (pinfunction "8_8") (pintype "passive"))
      (node (ref "U$5") (pin "8") (pinfunction "8_8") (pintype "passive"))
    )
    (net (code "40") (name "/PWM_TFT") (class "Default")
      (node (ref "PCB2") (pin "13") (pinfunction "13_13") (pintype "bidirectional"))
      (node (ref "U$3") (pin "LITE") (pinfunction "LITE_LITE") (pintype "bidirectional"))
    )
    (net (code "41") (name "/RL1") (class "Default")
      (node (ref "C4") (pin "2") (pinfunction "2_2") (pintype "passive"))
      (node (ref "K5") (pin "2") (pinfunction "2_2") (pintype "passive"))
      (node (ref "RL_DR1") (pin "15") (pinfunction "4C_15") (pintype "output"))
    )
    (net (code "42") (name "/RL2") (class "Default")
      (node (ref "C6") (pin "2") (pinfunction "2_2") (pintype "passive"))
      (node (ref "K3") (pin "2") (pinfunction "2_2") (pintype "passive"))
      (node (ref "RL_DR1") (pin "14") (pinfunction "5C_14") (pintype "output"))
    )
    (net (code "43") (name "/RL3") (class "Default")
      (node (ref "C13") (pin "2") (pinfunction "2_2") (pintype "passive"))
      (node (ref "K7") (pin "10") (pinfunction "2_10") (pintype "passive"))
      (node (ref "RL_DR1") (pin "13") (pinfunction "6C_13") (pintype "output"))
    )
    (net (code "44") (name "/RL4") (class "Default")
      (node (ref "C2") (pin "2") (pinfunction "2_2") (pintype "passive"))
      (node (ref "K4") (pin "10") (pinfunction "2_10") (pintype "passive"))
      (node (ref "RL_DR1") (pin "12") (pinfunction "7C_12") (pintype "output"))
    )
    (net (code "45") (name "/RL5") (class "Default")
      (node (ref "C5") (pin "2") (pinfunction "2_2") (pintype "passive"))
      (node (ref "K1") (pin "10") (pinfunction "2_10") (pintype "passive"))
      (node (ref "RL_DR1") (pin "11") (pinfunction "8C_11") (pintype "output"))
    )
    (net (code "46") (name "/SCK") (class "Default")
      (node (ref "PCB2") (pin "52") (pinfunction "52_52") (pintype "bidirectional"))
      (node (ref "U$1") (pin "5") (pinfunction "5_5") (pintype "passive"))
      (node (ref "U$3") (pin "SCK") (pinfunction "SCK_SCK") (pintype "bidirectional"))
      (node (ref "U$5") (pin "5") (pinfunction "5_5") (pintype "passive"))
    )
    (net (code "47") (name "/SW_ENC1") (class "Default")
      (node (ref "C32") (pin "2") (pinfunction "2_2") (pintype "passive"))
      (node (ref "PCB2") (pin "2") (pinfunction "2_2") (pintype "bidirectional"))
      (node (ref "R27") (pin "1") (pinfunction "1_1") (pintype "passive"))
    )
    (net (code "48") (name "/SW_ENC2") (class "Default")
      (node (ref "C33") (pin "2") (pinfunction "2_2") (pintype "passive"))
      (node (ref "PCB2") (pin "3") (pinfunction "3_3") (pintype "bidirectional"))
      (node (ref "R28") (pin "2") (pinfunction "2_2") (pintype "passive"))
    )
    (net (code "49") (name "/SW_PUSH") (class "Default")
      (node (ref "C31") (pin "2") (pinfunction "2_2") (pintype "passive"))
      (node (ref "PCB2") (pin "19") (pinfunction "19(RX1)_19") (pintype "bidirectional"))
      (node (ref "R6") (pin "1") (pinfunction "1_1") (pintype "passive"))
    )
    (net (code "50") (name "/TFT_CS") (class "Default")
      (node (ref "PCB2") (pin "11") (pinfunction "11_11") (pintype "bidirectional"))
      (node (ref "U$3") (pin "CS") (pinfunction "CS_CS") (pintype "bidirectional"))
    )
    (net (code "51") (name "/TFT_INT") (class "Default")
      (node (ref "PCB2") (pin "18") (pinfunction "18(TX1)_18") (pintype "bidirectional"))
      (node (ref "U$3") (pin "INT") (pinfunction "INT_INT") (pintype "bidirectional"))
    )
    (net (code "52") (name "/TFT_RST") (class "Default")
      (node (ref "PCB2") (pin "8") (pinfunction "8_8") (pintype "bidirectional"))
      (node (ref "U$3") (pin "RST") (pinfunction "RST_RST") (pintype "bidirectional"))
    )
    (net (code "53") (name "/TFT_WAIT") (class "Default")
      (node (ref "PCB2") (pin "9") (pinfunction "9_9") (pintype "bidirectional"))
      (node (ref "U$3") (pin "WAIT") (pinfunction "WAIT_WAIT") (pintype "bidirectional"))
    )
    (net (code "54") (name "/TFT_X+") (class "Default")
      (node (ref "PCB2") (pin "A6") (pinfunction "A6_A6") (pintype "bidirectional"))
      (node (ref "U$3") (pin "X+") (pinfunction "X+_X+") (pintype "bidirectional"))
    )
    (net (code "55") (name "/TFT_X-") (class "Default")
      (node (ref "PCB2") (pin "A7") (pinfunction "A7_A7") (pintype "bidirectional"))
      (node (ref "U$3") (pin "X-") (pinfunction "X-_X-") (pintype "bidirectional"))
    )
    (net (code "56") (name "/TFT_Y+") (class "Default")
      (node (ref "PCB2") (pin "A9") (pinfunction "A9_A9") (pintype "bidirectional"))
      (node (ref "U$3") (pin "Y+") (pinfunction "Y+_Y+") (pintype "bidirectional"))
    )
    (net (code "57") (name "/TFT_Y-") (class "Default")
      (node (ref "PCB2") (pin "A8") (pinfunction "A8_A8") (pintype "bidirectional"))
      (node (ref "U$3") (pin "Y-") (pinfunction "Y-_Y-") (pintype "bidirectional"))
    )
    (net (code "58") (name "/VOL_CS") (class "Default")
      (node (ref "PCB2") (pin "6") (pinfunction "6_6") (pintype "bidirectional"))
      (node (ref "U$1") (pin "4") (pinfunction "4_4") (pintype "passive"))
      (node (ref "U$5") (pin "4") (pinfunction "4_4") (pintype "passive"))
    )
    (net (code "59") (name "/V_RECT") (class "Default")
      (node (ref "C11") (pin "+") (pinfunction "+_+") (pintype "passive"))
      (node (ref "GBU6D") (pin "+") (pinfunction "+_+") (pintype "passive"))
      (node (ref "LM323T") (pin "1") (pinfunction "IN_1") (pintype "input"))
      (node (ref "OPT_SW4") (pin "1") (pinfunction "1_1") (pintype "bidirectional"))
    )
    (net (code "60") (name "/V_RECT1") (class "Default")
      (node (ref "K1") (pin "S1") (pinfunction "S_S1") (pintype "passive"))
      (node (ref "U$1") (pin "1") (pinfunction "1_1") (pintype "passive"))
    )
    (net (code "61") (name "/V_RECT2") (class "Default")
      (node (ref "K1") (pin "S2") (pinfunction "S_S2") (pintype "passive"))
      (node (ref "U$5") (pin "1") (pinfunction "1_1") (pintype "passive"))
    )
    (net (code "62") (name "/V_RECT_SEL") (class "Default")
      (node (ref "K1") (pin "P1") (pinfunction "P_P1") (pintype "passive"))
      (node (ref "K1") (pin "P2") (pinfunction "P_P2") (pintype "passive"))
      (node (ref "OPT_SW4") (pin "2") (pinfunction "2_2") (pintype "bidirectional"))
    )
    (net (code "63") (name "Net-(6V_TRF_PRIM-Pad1)") (class "Default")
      (node (ref "6V_TRF_PRIM") (pin "1") (pinfunction "1_1") (pintype "passive"))
      (node (ref "F1") (pin "2") (pinfunction "2_2") (pintype "passive"))
    )
    (net (code "64") (name "Net-(6V_TRF_SECB-1)") (class "Default")
      (node (ref "6V_TRF_SEC") (pin "1") (pinfunction "1_1") (pintype "passive"))
      (node (ref "6V_TRF_SEC") (pin "2") (pinfunction "1_2") (pintype "passive"))
      (node (ref "GBU6D") (pin "AC2") (pinfunction "AC1_AC2") (pintype "passive"))
    )
    (net (code "65") (name "Net-(6V_TRF_SECC-1)") (class "Default")
      (node (ref "6V_TRF_SEC") (pin "3") (pinfunction "1_3") (pintype "passive"))
      (node (ref "6V_TRF_SEC") (pin "4") (pinfunction "1_4") (pintype "passive"))
      (node (ref "GBU6D") (pin "AC1") (pinfunction "AC2_AC1") (pintype "passive"))
    )
    (net (code "66") (name "Net-(IR_LED_OUT-C)") (class "Default")
      (node (ref "IR_LED_OUT") (pin "K") (pinfunction "C_K") (pintype "passive"))
      (node (ref "R2") (pin "1") (pinfunction "1_1") (pintype "passive"))
    )
    (net (code "67") (name "Net-(K3B-P)") (class "Default")
      (node (ref "K3") (pin "P1") (pinfunction "P_P1") (pintype "passive"))
      (node (ref "X3") (pin "3") (pinfunction "1_3") (pintype "passive"))
    )
    (net (code "68") (name "Net-(K3C-P)") (class "Default")
      (node (ref "K3") (pin "P2") (pinfunction "P_P2") (pintype "passive"))
      (node (ref "X3") (pin "1") (pinfunction "1_1") (pintype "passive"))
    )
    (net (code "69") (name "Net-(K4B-O)") (class "Default")
      (node (ref "K4") (pin "O1") (pinfunction "O_O1") (pintype "passive"))
      (node (ref "OPT_SW2") (pin "3") (pinfunction "3_3") (pintype "bidirectional"))
    )
    (net (code "70") (name "Net-(K4B-P)") (class "Default")
      (node (ref "K4") (pin "P1") (pinfunction "P_P1") (pintype "passive"))
      (node (ref "OPT_SW2") (pin "2") (pinfunction "2_2") (pintype "bidirectional"))
    )
    (net (code "71") (name "Net-(K4B-S)") (class "Default")
      (node (ref "K4") (pin "S1") (pinfunction "S_S1") (pintype "passive"))
      (node (ref "OPT_SW2") (pin "1") (pinfunction "1_1") (pintype "bidirectional"))
    )
    (net (code "72") (name "Net-(K4C-O)") (class "Default")
      (node (ref "K4") (pin "O2") (pinfunction "O_O2") (pintype "passive"))
      (node (ref "OPT_SW3") (pin "3") (pinfunction "3_3") (pintype "bidirectional"))
    )
    (net (code "73") (name "Net-(K4C-S)") (class "Default")
      (node (ref "K4") (pin "S2") (pinfunction "S_S2") (pintype "passive"))
      (node (ref "OPT_SW3") (pin "1") (pinfunction "1_1") (pintype "bidirectional"))
    )
    (net (code "74") (name "Net-(K5B-P)") (class "Default")
      (node (ref "K5") (pin "P1") (pinfunction "P_P1") (pintype "passive"))
      (node (ref "X1") (pin "1") (pinfunction "1_1") (pintype "passive"))
      (node (ref "X2") (pin "1") (pinfunction "1_1") (pintype "passive"))
      (node (ref "X4") (pin "1") (pinfunction "1_1") (pintype "passive"))
      (node (ref "X5") (pin "1") (pinfunction "1_1") (pintype "passive"))
    )
    (net (code "75") (name "Net-(K5C-P)") (class "Default")
      (node (ref "K5") (pin "P2") (pinfunction "P_P2") (pintype "passive"))
      (node (ref "X1") (pin "3") (pinfunction "1_3") (pintype "passive"))
      (node (ref "X2") (pin "3") (pinfunction "1_3") (pintype "passive"))
      (node (ref "X4") (pin "3") (pinfunction "1_3") (pintype "passive"))
      (node (ref "X5") (pin "3") (pinfunction "1_3") (pintype "passive"))
    )
    (net (code "76") (name "Net-(K7B-O)") (class "Default")
      (node (ref "K7") (pin "O1") (pinfunction "O_O1") (pintype "passive"))
      (node (ref "OPT_SW") (pin "3") (pinfunction "3_3") (pintype "bidirectional"))
    )
    (net (code "77") (name "Net-(K7B-P)") (class "Default")
      (node (ref "K7") (pin "P1") (pinfunction "P_P1") (pintype "passive"))
      (node (ref "OPT_SW") (pin "2") (pinfunction "2_2") (pintype "bidirectional"))
    )
    (net (code "78") (name "Net-(K7B-S)") (class "Default")
      (node (ref "K7") (pin "S1") (pinfunction "S_S1") (pintype "passive"))
      (node (ref "OPT_SW") (pin "1") (pinfunction "1_1") (pintype "bidirectional"))
    )
    (net (code "79") (name "Net-(K7C-O)") (class "Default")
      (node (ref "K7") (pin "O2") (pinfunction "O_O2") (pintype "passive"))
      (node (ref "OPT_SW1") (pin "3") (pinfunction "3_3") (pintype "bidirectional"))
    )
    (net (code "80") (name "Net-(K7C-S)") (class "Default")
      (node (ref "K7") (pin "S2") (pinfunction "S_S2") (pintype "passive"))
      (node (ref "OPT_SW1") (pin "1") (pinfunction "1_1") (pintype "bidirectional"))
    )
    (net (code "81") (name "Net-(LED_DR1-1C)") (class "Default")
      (node (ref "LED_DR1") (pin "18") (pinfunction "1C_18") (pintype "output"))
      (node (ref "R12") (pin "2") (pinfunction "2_2") (pintype "passive"))
    )
    (net (code "82") (name "Net-(LED_DR1-2C)") (class "Default")
      (node (ref "LED_DR1") (pin "17") (pinfunction "2C_17") (pintype "output"))
      (node (ref "R11") (pin "2") (pinfunction "2_2") (pintype "passive"))
    )
    (net (code "83") (name "Net-(LED_DR1-3C)") (class "Default")
      (node (ref "LED_DR1") (pin "16") (pinfunction "3C_16") (pintype "output"))
      (node (ref "R10") (pin "2") (pinfunction "2_2") (pintype "passive"))
    )
    (net (code "84") (name "Net-(LED_DR1-4C)") (class "Default")
      (node (ref "LED_DR1") (pin "15") (pinfunction "4C_15") (pintype "output"))
      (node (ref "R9") (pin "2") (pinfunction "2_2") (pintype "passive"))
    )
    (net (code "85") (name "Net-(LED_DR1-5C)") (class "Default")
      (node (ref "LED_DR1") (pin "14") (pinfunction "5C_14") (pintype "output"))
      (node (ref "R8") (pin "2") (pinfunction "2_2") (pintype "passive"))
    )
    (net (code "86") (name "Net-(LED_DR1-6C)") (class "Default")
      (node (ref "LED_DR1") (pin "13") (pinfunction "6C_13") (pintype "output"))
      (node (ref "R7") (pin "2") (pinfunction "2_2") (pintype "passive"))
    )
    (net (code "87") (name "Net-(LED_DR1-7C)") (class "Default")
      (node (ref "LED_DR1") (pin "12") (pinfunction "7C_12") (pintype "output"))
      (node (ref "R4") (pin "2") (pinfunction "2_2") (pintype "passive"))
    )
    (net (code "88") (name "Net-(LED_DR1-8C)") (class "Default")
      (node (ref "LED_DR1") (pin "11") (pinfunction "8C_11") (pintype "output"))
      (node (ref "R5") (pin "2") (pinfunction "2_2") (pintype "passive"))
    )
    (net (code "89") (name "Net-(LED_DR2-1C)") (class "Default")
      (node (ref "LED_DR2") (pin "18") (pinfunction "1C_18") (pintype "output"))
      (node (ref "R20") (pin "2") (pinfunction "2_2") (pintype "passive"))
    )
    (net (code "90") (name "Net-(LED_DR2-2C)") (class "Default")
      (node (ref "LED_DR2") (pin "17") (pinfunction "2C_17") (pintype "output"))
      (node (ref "R19") (pin "2") (pinfunction "2_2") (pintype "passive"))
    )
    (net (code "91") (name "Net-(LED_DR2-3C)") (class "Default")
      (node (ref "LED_DR2") (pin "16") (pinfunction "3C_16") (pintype "output"))
      (node (ref "R18") (pin "2") (pinfunction "2_2") (pintype "passive"))
    )
    (net (code "92") (name "Net-(LED_DR2-4C)") (class "Default")
      (node (ref "LED_DR2") (pin "15") (pinfunction "4C_15") (pintype "output"))
      (node (ref "R17") (pin "2") (pinfunction "2_2") (pintype "passive"))
    )
    (net (code "93") (name "Net-(LED_DR2-5C)") (class "Default")
      (node (ref "LED_DR2") (pin "14") (pinfunction "5C_14") (pintype "output"))
      (node (ref "R16") (pin "2") (pinfunction "2_2") (pintype "passive"))
    )
    (net (code "94") (name "Net-(LED_DR2-6C)") (class "Default")
      (node (ref "LED_DR2") (pin "13") (pinfunction "6C_13") (pintype "output"))
      (node (ref "R15") (pin "2") (pinfunction "2_2") (pintype "passive"))
    )
    (net (code "95") (name "Net-(LED_DR2-7C)") (class "Default")
      (node (ref "LED_DR2") (pin "12") (pinfunction "7C_12") (pintype "output"))
      (node (ref "R14") (pin "2") (pinfunction "2_2") (pintype "passive"))
    )
    (net (code "96") (name "Net-(LED_DR2-8C)") (class "Default")
      (node (ref "LED_DR2") (pin "11") (pinfunction "8C_11") (pintype "output"))
      (node (ref "R13") (pin "2") (pinfunction "2_2") (pintype "passive"))
    )
    (net (code "97") (name "Net-(LED_VOL1-C)") (class "Default")
      (node (ref "LED_VOL1") (pin "K") (pinfunction "C_K") (pintype "passive"))
      (node (ref "R12") (pin "1") (pinfunction "1_1") (pintype "passive"))
    )
    (net (code "98") (name "Net-(LED_VOL1-PadA)") (class "Default")
      (node (ref "LED_VOL1") (pin "A") (pinfunction "A_A") (pintype "passive"))
      (node (ref "LED_VOL2") (pin "A") (pinfunction "A_A") (pintype "passive"))
      (node (ref "LED_VOL3") (pin "A") (pinfunction "A_A") (pintype "passive"))
      (node (ref "LED_VOL4") (pin "A") (pinfunction "A_A") (pintype "passive"))
      (node (ref "LED_VOL5") (pin "A") (pinfunction "A_A") (pintype "passive"))
      (node (ref "LED_VOL6") (pin "A") (pinfunction "A_A") (pintype "passive"))
      (node (ref "LED_VOL7") (pin "A") (pinfunction "A_A") (pintype "passive"))
      (node (ref "LED_VOL8") (pin "A") (pinfunction "A_A") (pintype "passive"))
      (node (ref "Q2") (pin "D") (pinfunction "D_D") (pintype "passive"))
      (node (ref "R26") (pin "2") (pinfunction "2_2") (pintype "passive"))
    )
    (net (code "99") (name "Net-(LED_VOL2-C)") (class "Default")
      (node (ref "LED_VOL2") (pin "K") (pinfunction "C_K") (pintype "passive"))
      (node (ref "R11") (pin "1") (pinfunction "1_1") (pintype "passive"))
    )
    (net (code "100") (name "Net-(LED_VOL3-C)") (class "Default")
      (node (ref "LED_VOL3") (pin "K") (pinfunction "C_K") (pintype "passive"))
      (node (ref "R10") (pin "1") (pinfunction "1_1") (pintype "passive"))
    )
    (net (code "101") (name "Net-(LED_VOL4-C)") (class "Default")
      (node (ref "LED_VOL4") (pin "K") (pinfunction "C_K") (pintype "passive"))
      (node (ref "R9") (pin "1") (pinfunction "1_1") (pintype "passive"))
    )
    (net (code "102") (name "Net-(LED_VOL5-C)") (class "Default")
      (node (ref "LED_VOL5") (pin "K") (pinfunction "C_K") (pintype "passive"))
      (node (ref "R8") (pin "1") (pinfunction "1_1") (pintype "passive"))
    )
    (net (code "103") (name "Net-(LED_VOL6-C)") (class "Default")
      (node (ref "LED_VOL6") (pin "K") (pinfunction "C_K") (pintype "passive"))
      (node (ref "R7") (pin "1") (pinfunction "1_1") (pintype "passive"))
    )
    (net (code "104") (name "Net-(LED_VOL7-C)") (class "Default")
      (node (ref "LED_VOL7") (pin "K") (pinfunction "C_K") (pintype "passive"))
      (node (ref "R4") (pin "1") (pinfunction "1_1") (pintype "passive"))
    )
    (net (code "105") (name "Net-(LED_VOL8-C)") (class "Default")
      (node (ref "LED_VOL8") (pin "K") (pinfunction "C_K") (pintype "passive"))
      (node (ref "R5") (pin "1") (pinfunction "1_1") (pintype "passive"))
    )
    (net (code "106") (name "Net-(LED_VOL9-C)") (class "Default")
      (node (ref "LED_VOL9") (pin "K") (pinfunction "C_K") (pintype "passive"))
      (node (ref "R13") (pin "1") (pinfunction "1_1") (pintype "passive"))
    )
    (net (code "107") (name "Net-(LED_VOL10-C)") (class "Default")
      (node (ref "LED_VOL10") (pin "K") (pinfunction "C_K") (pintype "passive"))
      (node (ref "R14") (pin "1") (pinfunction "1_1") (pintype "passive"))
    )
    (net (code "108") (name "Net-(LED_VOL10-PadA)") (class "Default")
      (node (ref "LED_VOL10") (pin "A") (pinfunction "A_A") (pintype "passive"))
      (node (ref "LED_VOL11") (pin "A") (pinfunction "A_A") (pintype "passive"))
      (node (ref "LED_VOL12") (pin "A") (pinfunction "A_A") (pintype "passive"))
      (node (ref "LED_VOL13") (pin "A") (pinfunction "A_A") (pintype "passive"))
      (node (ref "LED_VOL14") (pin "A") (pinfunction "A_A") (pintype "passive"))
      (node (ref "LED_VOL15") (pin "A") (pinfunction "A_A") (pintype "passive"))
      (node (ref "LED_VOL16") (pin "A") (pinfunction "A_A") (pintype "passive"))
      (node (ref "LED_VOL9") (pin "A") (pinfunction "A_A") (pintype "passive"))
      (node (ref "Q1") (pin "D") (pinfunction "D_D") (pintype "passive"))
      (node (ref "R3") (pin "2") (pinfunction "2_2") (pintype "passive"))
    )
    (net (code "109") (name "Net-(LED_VOL11-C)") (class "Default")
      (node (ref "LED_VOL11") (pin "K") (pinfunction "C_K") (pintype "passive"))
      (node (ref "R15") (pin "1") (pinfunction "1_1") (pintype "passive"))
    )
    (net (code "110") (name "Net-(LED_VOL12-C)") (class "Default")
      (node (ref "LED_VOL12") (pin "K") (pinfunction "C_K") (pintype "passive"))
      (node (ref "R16") (pin "1") (pinfunction "1_1") (pintype "passive"))
    )
    (net (code "111") (name "Net-(LED_VOL13-C)") (class "Default")
      (node (ref "LED_VOL13") (pin "K") (pinfunction "C_K") (pintype "passive"))
      (node (ref "R17") (pin "1") (pinfunction "1_1") (pintype "passive"))
    )
    (net (code "112") (name "Net-(LED_VOL14-C)") (class "Default")
      (node (ref "LED_VOL14") (pin "K") (pinfunction "C_K") (pintype "passive"))
      (node (ref "R18") (pin "1") (pinfunction "1_1") (pintype "passive"))
    )
    (net (code "113") (name "Net-(LED_VOL15-C)") (class "Default")
      (node (ref "LED_VOL15") (pin "K") (pinfunction "C_K") (pintype "passive"))
      (node (ref "R19") (pin "1") (pinfunction "1_1") (pintype "passive"))
    )
    (net (code "114") (name "Net-(LED_VOL16-C)") (class "Default")
      (node (ref "LED_VOL16") (pin "K") (pinfunction "C_K") (pintype "passive"))
      (node (ref "R20") (pin "1") (pinfunction "1_1") (pintype "passive"))
    )
    (net (code "115") (name "Net-(PCB2-14(TX3))") (class "Default")
      (node (ref "PCB2") (pin "14") (pinfunction "14(TX3)_14") (pintype "bidirectional"))
      (node (ref "SERIAL_COM") (pin "1") (pinfunction "1_1") (pintype "bidirectional"))
    )
    (net (code "116") (name "Net-(PCB2-15(RX3))") (class "Default")
      (node (ref "PCB2") (pin "15") (pinfunction "15(RX3)_15") (pintype "bidirectional"))
      (node (ref "SERIAL_COM") (pin "2") (pinfunction "2_2") (pintype "bidirectional"))
    )
    (net (code "117") (name "Net-(PCB2-16(TX2))") (class "Default")
      (node (ref "PCB2") (pin "16") (pinfunction "16(TX2)_16") (pintype "bidirectional"))
      (node (ref "SERIAL_COM1") (pin "1") (pinfunction "1_1") (pintype "bidirectional"))
    )
    (net (code "118") (name "Net-(PCB2-17(RX2))") (class "Default")
      (node (ref "PCB2") (pin "17") (pinfunction "17(RX2)_17") (pintype "bidirectional"))
      (node (ref "SERIAL_COM1") (pin "2") (pinfunction "2_2") (pintype "bidirectional"))
    )
    (net (code "119") (name "Net-(PCB2-PadA0)") (class "Default")
      (node (ref "PCB2") (pin "A0") (pinfunction "A0_A0") (pintype "bidirectional"))
      (node (ref "U$1") (pin "9") (pinfunction "9_9") (pintype "passive"))
    )
    (net (code "120") (name "Net-(PCB2-PadA1)") (class "Default")
      (node (ref "PCB2") (pin "A1") (pinfunction "A1_A1") (pintype "bidirectional"))
      (node (ref "U$1") (pin "10") (pinfunction "10_10") (pintype "passive"))
    )
    (net (code "121") (name "Net-(PCB2-PadA2)") (class "Default")
      (node (ref "PCB2") (pin "A2") (pinfunction "A2_A2") (pintype "bidirectional"))
      (node (ref "U$5") (pin "9") (pinfunction "9_9") (pintype "passive"))
    )
    (net (code "122") (name "Net-(PCB2-PadA3)") (class "Default")
      (node (ref "PCB2") (pin "A3") (pinfunction "A3_A3") (pintype "bidirectional"))
      (node (ref "U$5") (pin "10") (pinfunction "10_10") (pintype "passive"))
    )
    (net (code "123") (name "Net-(PWR_LED-Pad1)") (class "Default")
      (node (ref "PWR_LED") (pin "1") (pinfunction "1_1") (pintype "bidirectional"))
      (node (ref "R31") (pin "1") (pinfunction "1_1") (pintype "passive"))
    )
    (net (code "124") (name "Net-(R22-Pad2)") (class "Default")
      (node (ref "R22") (pin "2") (pinfunction "2_2") (pintype "passive"))
      (node (ref "R27") (pin "2") (pinfunction "2_2") (pintype "passive"))
      (node (ref "SW2") (pin "B") (pinfunction "B_B") (pintype "passive"))
    )
    (net (code "125") (name "Net-(R23-Pad2)") (class "Default")
      (node (ref "R23") (pin "2") (pinfunction "2_2") (pintype "passive"))
      (node (ref "R28") (pin "1") (pinfunction "1_1") (pintype "passive"))
      (node (ref "SW2") (pin "A") (pinfunction "A_A") (pintype "passive"))
    )
    (net (code "126") (name "Net-(RL_DR1-3C)") (class "Default")
      (node (ref "R2") (pin "2") (pinfunction "2_2") (pintype "passive"))
      (node (ref "RL_DR1") (pin "16") (pinfunction "3C_16") (pintype "output"))
    )
    (net (code "127") (name "Net-(SW2B-2)") (class "Default")
      (node (ref "R21") (pin "2") (pinfunction "2_2") (pintype "passive"))
      (node (ref "R6") (pin "2") (pinfunction "2_2") (pintype "passive"))
      (node (ref "SW2") (pin "E") (pinfunction "2_E") (pintype "passive"))
    )
    (net (code "128") (name "unconnected-(H1-MOUNT-PadB3,0)") (class "Default")
      (node (ref "H1") (pin "B3,0") (pinfunction "MOUNT_B3,0") (pintype "passive"))
    )
    (net (code "129") (name "unconnected-(H3-MOUNT-PadB3,0)") (class "Default")
      (node (ref "H3") (pin "B3,0") (pinfunction "MOUNT_B3,0") (pintype "passive"))
    )
    (net (code "130") (name "unconnected-(H6-MOUNT-PadB3,0)") (class "Default")
      (node (ref "H6") (pin "B3,0") (pinfunction "MOUNT_B3,0") (pintype "passive"))
    )
    (net (code "131") (name "unconnected-(H7-MOUNT-PadB3,0)") (class "Default")
      (node (ref "H7") (pin "B3,0") (pinfunction "MOUNT_B3,0") (pintype "passive"))
    )
    (net (code "132") (name "unconnected-(H8-MOUNT-PadB3,0)") (class "Default")
      (node (ref "H8") (pin "B3,0") (pinfunction "MOUNT_B3,0") (pintype "passive"))
    )
    (net (code "133") (name "unconnected-(H9-MOUNT-PadB3,0)") (class "Default")
      (node (ref "H9") (pin "B3,0") (pinfunction "MOUNT_B3,0") (pintype "passive"))
    )
    (net (code "134") (name "unconnected-(K1B-O-PadO1)") (class "Default")
      (node (ref "K1") (pin "O1") (pinfunction "O_O1") (pintype "passive"))
    )
    (net (code "135") (name "unconnected-(K1C-O-PadO2)") (class "Default")
      (node (ref "K1") (pin "O2") (pinfunction "O_O2") (pintype "passive"))
    )
    (net (code "136") (name "unconnected-(K3B-O-PadO1)") (class "Default")
      (node (ref "K3") (pin "O1") (pinfunction "O_O1") (pintype "passive"))
    )
    (net (code "137") (name "unconnected-(K3C-O-PadO2)") (class "Default")
      (node (ref "K3") (pin "O2") (pinfunction "O_O2") (pintype "passive"))
    )
    (net (code "138") (name "unconnected-(K5B-O-PadO1)") (class "Default")
      (node (ref "K5") (pin "O1") (pinfunction "O_O1") (pintype "passive"))
    )
    (net (code "139") (name "unconnected-(K5C-O-PadO2)") (class "Default")
      (node (ref "K5") (pin "O2") (pinfunction "O_O2") (pintype "passive"))
    )
    (net (code "140") (name "unconnected-(PCB2-(N{slash}C)-PadN{slash}C)") (class "Default")
      (node (ref "PCB2") (pin "N/C") (pinfunction "(N/C)_N/C") (pintype "bidirectional"))
    )
    (net (code "141") (name "unconnected-(PCB2-0(RX)-Pad0)") (class "Default")
      (node (ref "PCB2") (pin "0") (pinfunction "0(RX)_0") (pintype "bidirectional"))
    )
    (net (code "142") (name "unconnected-(PCB2-1(TX)-Pad1)") (class "Default")
      (node (ref "PCB2") (pin "1") (pinfunction "1(TX)_1") (pintype "bidirectional"))
    )
    (net (code "143") (name "unconnected-(PCB2-20(SDA)-Pad20)") (class "Default")
      (node (ref "PCB2") (pin "20") (pinfunction "20(SDA)_20") (pintype "bidirectional"))
    )
    (net (code "144") (name "unconnected-(PCB2-21(SCL)-Pad21)") (class "Default")
      (node (ref "PCB2") (pin "21") (pinfunction "21(SCL)_21") (pintype "bidirectional"))
    )
    (net (code "145") (name "unconnected-(PCB2-IOREF-PadI{slash}OREF)") (class "Default")
      (node (ref "PCB2") (pin "I/OREF") (pinfunction "IOREF_I/OREF") (pintype "bidirectional"))
    )
    (net (code "146") (name "unconnected-(PCB2-Pad3.3V)") (class "Default")
      (node (ref "PCB2") (pin "3.3V") (pinfunction "3.3V_3.3V") (pintype "bidirectional"))
    )
    (net (code "147") (name "unconnected-(PCB2-Pad4)") (class "Default")
      (node (ref "PCB2") (pin "4") (pinfunction "4_4") (pintype "bidirectional"))
    )
    (net (code "148") (name "unconnected-(PCB2-Pad53)") (class "Default")
      (node (ref "PCB2") (pin "53") (pinfunction "53_53") (pintype "bidirectional"))
    )
    (net (code "149") (name "unconnected-(PCB2-PadA4)") (class "Default")
      (node (ref "PCB2") (pin "A4") (pinfunction "A4_A4") (pintype "bidirectional"))
    )
    (net (code "150") (name "unconnected-(PCB2-PadA5)") (class "Default")
      (node (ref "PCB2") (pin "A5") (pinfunction "A5_A5") (pintype "bidirectional"))
    )
    (net (code "151") (name "unconnected-(PCB2-PadA10)") (class "Default")
      (node (ref "PCB2") (pin "A10") (pinfunction "A10_A10") (pintype "bidirectional"))
    )
    (net (code "152") (name "unconnected-(PCB2-PadA11)") (class "Default")
      (node (ref "PCB2") (pin "A11") (pinfunction "A11_A11") (pintype "bidirectional"))
    )
    (net (code "153") (name "unconnected-(PCB2-PadA12)") (class "Default")
      (node (ref "PCB2") (pin "A12") (pinfunction "A12_A12") (pintype "bidirectional"))
    )
    (net (code "154") (name "unconnected-(PCB2-PadA13)") (class "Default")
      (node (ref "PCB2") (pin "A13") (pinfunction "A13_A13") (pintype "bidirectional"))
    )
    (net (code "155") (name "unconnected-(PCB2-PadA14)") (class "Default")
      (node (ref "PCB2") (pin "A14") (pinfunction "A14_A14") (pintype "bidirectional"))
    )
    (net (code "156") (name "unconnected-(PCB2-PadA15)") (class "Default")
      (node (ref "PCB2") (pin "A15") (pinfunction "A15_A15") (pintype "bidirectional"))
    )
    (net (code "157") (name "unconnected-(PCB2-PadGND)") (class "Default")
      (node (ref "PCB2") (pin "GND") (pinfunction "GND_GND") (pintype "bidirectional"))
    )
    (net (code "158") (name "unconnected-(PCB2-PadRESET)") (class "Default")
      (node (ref "PCB2") (pin "RESET") (pinfunction "RESET_RESET") (pintype "bidirectional"))
    )
    (net (code "159") (name "unconnected-(PCB2-PadSCL1)") (class "Default")
      (node (ref "PCB2") (pin "SCL1") (pinfunction "SCL1_SCL1") (pintype "bidirectional"))
    )
    (net (code "160") (name "unconnected-(PCB2-PadSDA1)") (class "Default")
      (node (ref "PCB2") (pin "SDA1") (pinfunction "SDA1_SDA1") (pintype "bidirectional"))
    )
    (net (code "161") (name "unconnected-(PCB2-PadVIN)") (class "Default")
      (node (ref "PCB2") (pin "VIN") (pinfunction "VIN_VIN") (pintype "bidirectional"))
    )
    (net (code "162") (name "unconnected-(PWR_LED-Pad2)") (class "Default")
      (node (ref "PWR_LED") (pin "2") (pinfunction "2_2") (pintype "bidirectional"))
    )
    (net (code "163") (name "unconnected-(RL_DR1-1B-Pad1)") (class "Default")
      (node (ref "RL_DR1") (pin "1") (pinfunction "1B_1") (pintype "input"))
    )
    (net (code "164") (name "unconnected-(RL_DR1-1C-Pad18)") (class "Default")
      (node (ref "RL_DR1") (pin "18") (pinfunction "1C_18") (pintype "output"))
    )
    (net (code "165") (name "unconnected-(RL_DR1-2B-Pad2)") (class "Default")
      (node (ref "RL_DR1") (pin "2") (pinfunction "2B_2") (pintype "input"))
    )
    (net (code "166") (name "unconnected-(RL_DR1-2C-Pad17)") (class "Default")
      (node (ref "RL_DR1") (pin "17") (pinfunction "2C_17") (pintype "output"))
    )
    (net (code "167") (name "unconnected-(U$3-Pad3VO)") (class "Default")
      (node (ref "U$3") (pin "3VO") (pinfunction "3VO_3VO") (pintype "bidirectional"))
    )
  )
)
